# LS.net
KiCad netlist of a schematic drawn in EAGLE
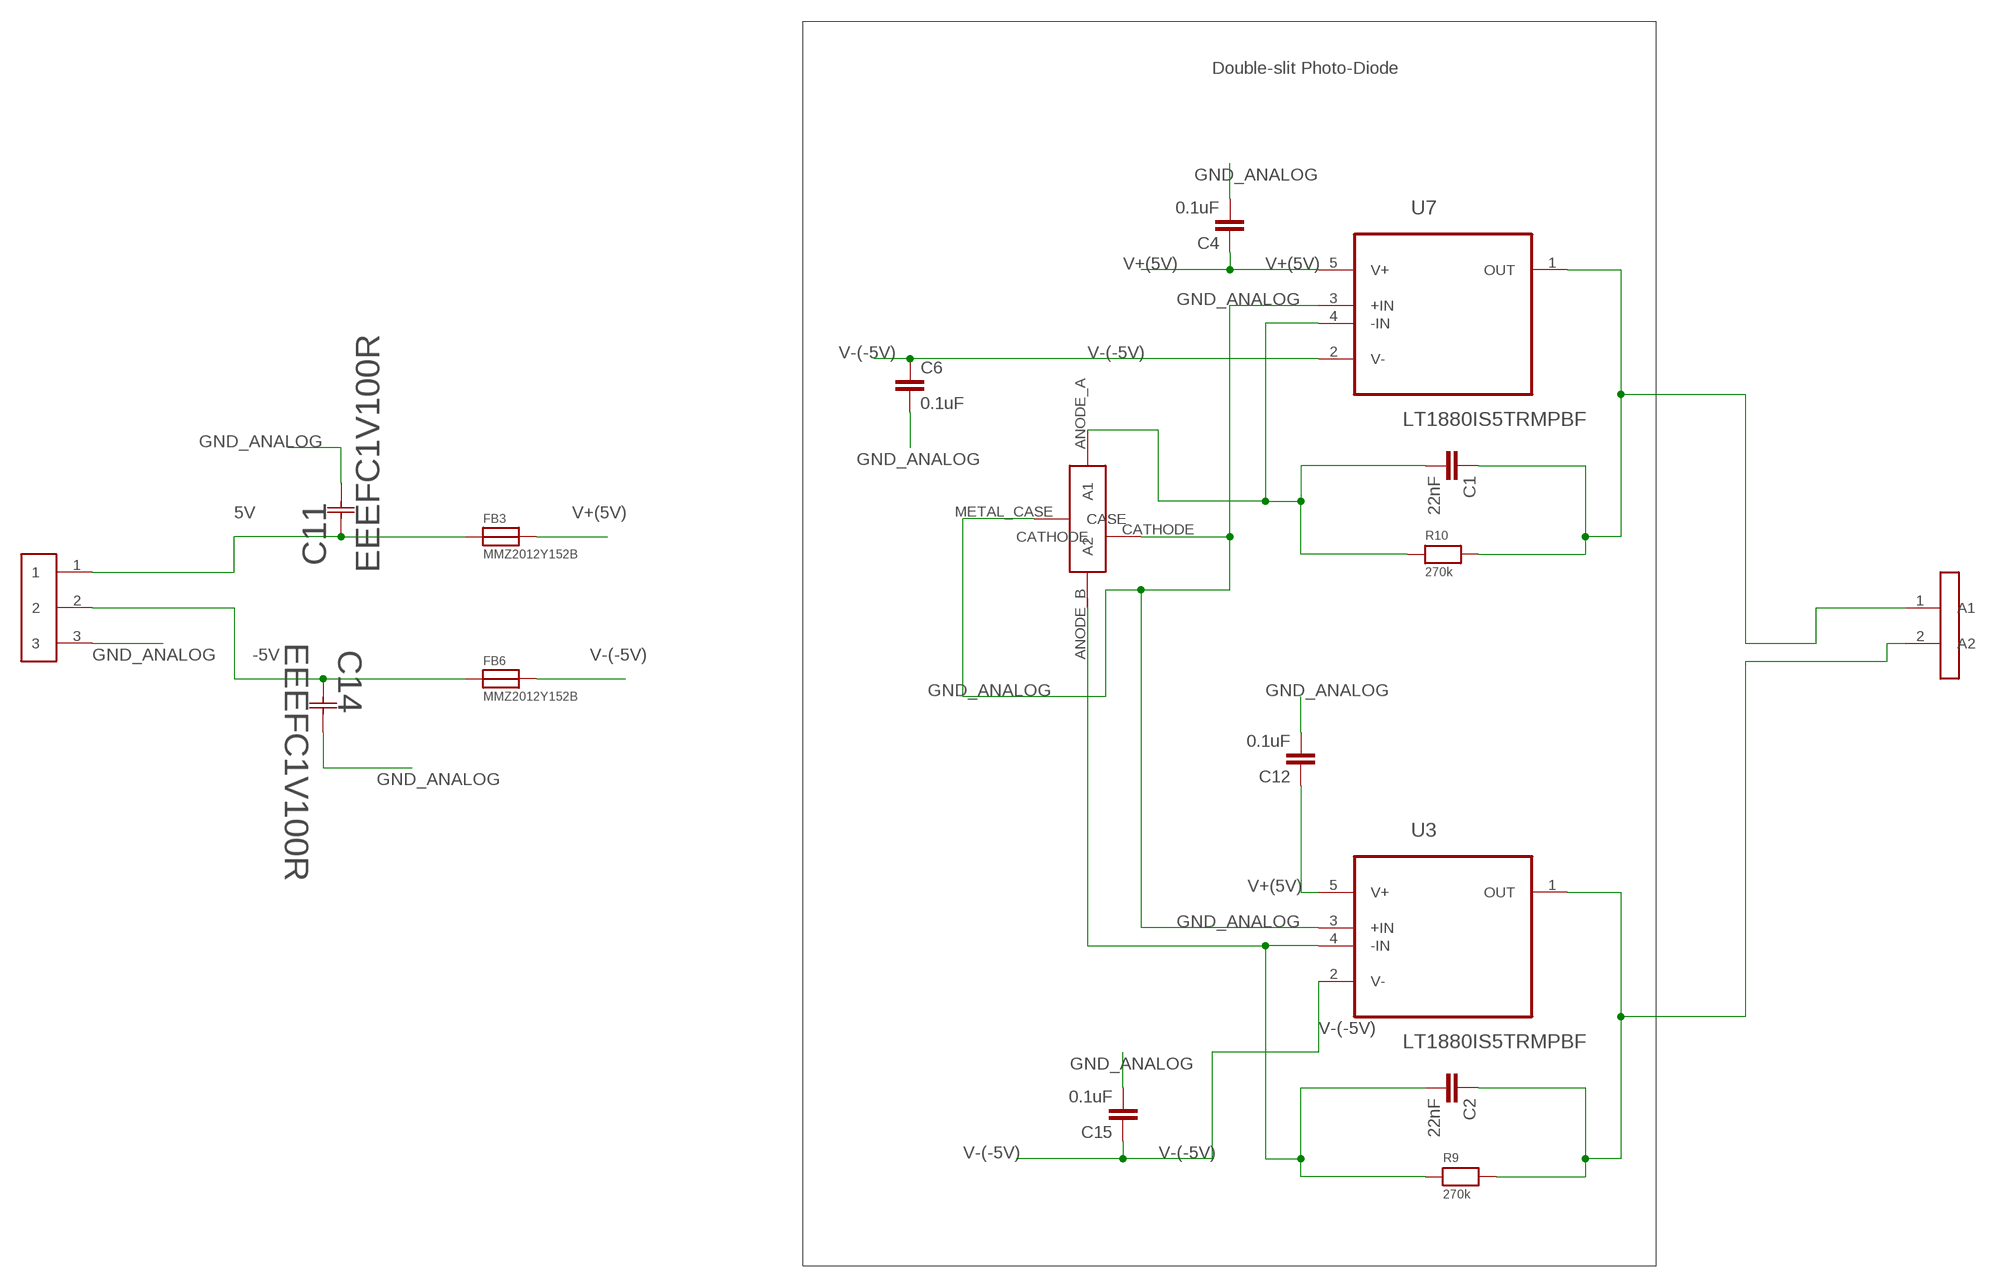
[diagram p0: schematic, sheet 1]

(export (version "E")
  (design (tool "Eeschema 10.0.6"))
  (components
    (comp (ref "C1")
      (value "22nF")
      (footprint "eagle-import:C0603")
      (libsource (lib "eagle-import") (part "C-EUC0603"))
    )
    (comp (ref "C2")
      (value "22nF")
      (footprint "eagle-import:C0603")
      (libsource (lib "eagle-import") (part "C-EUC0603"))
    )
    (comp (ref "C4")
      (value "0.1uF")
      (footprint "eagle-import:C0603")
      (libsource (lib "eagle-import") (part "C-EUC0603"))
    )
    (comp (ref "C6")
      (value "0.1uF")
      (footprint "eagle-import:C0603")
      (libsource (lib "eagle-import") (part "C-EUC0603"))
    )
    (comp (ref "C11")
      (value "EEEFC1V100R")
      (footprint "eagle-import:CAP_EEFC_C")
      (libsource (lib "eagle-import") (part "EEEFC1V100R"))
    )
    (comp (ref "C12")
      (value "0.1uF")
      (footprint "eagle-import:C0603")
      (libsource (lib "eagle-import") (part "C-EUC0603"))
    )
    (comp (ref "C14")
      (value "EEEFC1V100R")
      (footprint "eagle-import:CAP_EEFC_C")
      (libsource (lib "eagle-import") (part "EEEFC1V100R"))
    )
    (comp (ref "C15")
      (value "0.1uF")
      (footprint "eagle-import:C0603")
      (libsource (lib "eagle-import") (part "C-EUC0603"))
    )
    (comp (ref "FB3")
      (value "MMZ2012Y152B")
      (footprint "eagle-import:0805")
      (libsource (lib "eagle-import") (part "FERRITE0805"))
    )
    (comp (ref "FB6")
      (value "MMZ2012Y152B")
      (footprint "eagle-import:0805")
      (libsource (lib "eagle-import") (part "FERRITE0805"))
    )
    (comp (ref "J2")
      (value "22-28-8020")
      (footprint "eagle-import:22-28-8020")
      (fields (field (name "MANUFACTURER_PART_NUMBER") "22288020"))
      (libsource (lib "eagle-import") (part "22-28-8020"))
    )
    (comp (ref "R9")
      (value "270k")
      (footprint "eagle-import:0805")
      (libsource (lib "eagle-import") (part "RESISTOR0805"))
    )
    (comp (ref "R10")
      (value "270k")
      (footprint "eagle-import:0805")
      (libsource (lib "eagle-import") (part "RESISTOR0805"))
    )
    (comp (ref "U$1")
      (value "SFH221")
      (footprint "eagle-import:SFH_221")
      (libsource (lib "eagle-import") (part "SFH221"))
    )
    (comp (ref "U$2")
      (value "PINHD_SMD-3")
      (footprint "eagle-import:PINHD_SMD-3")
      (libsource (lib "eagle-import") (part "PINHD_SMD-3"))
    )
    (comp (ref "U3")
      (value "LT1880IS5TRMPBF")
      (footprint "eagle-import:SOT95P280X100-5N")
      (fields
        (field (name "DIGI-KEY_PART_NUMBER") "LT1880IS5#TRMPBFCT-ND")
        (field (name "MF") "Linear Technology")
        (field (name "MP") "LT1880IS5#TRMPBF")
      )
      (libsource (lib "eagle-import") (part "LT1880IS5TRMPBF"))
    )
    (comp (ref "U7")
      (value "LT1880IS5TRMPBF")
      (footprint "eagle-import:SOT95P280X100-5N")
      (fields
        (field (name "DIGI-KEY_PART_NUMBER") "LT1880IS5#TRMPBFCT-ND")
        (field (name "MF") "Linear Technology")
        (field (name "MP") "LT1880IS5#TRMPBF")
      )
      (libsource (lib "eagle-import") (part "LT1880IS5TRMPBF"))
    )
  )
  (nets
    (net (code "1") (name "/-5V") (class "Default")
      (node (ref "C14") (pin "1") (pinfunction "11_1") (pintype "passive"))
      (node (ref "FB6") (pin "1") (pinfunction "P$1_1") (pintype "bidirectional"))
      (node (ref "U$2") (pin "2") (pinfunction "2_2") (pintype "bidirectional"))
    )
    (net (code "2") (name "/5V") (class "Default")
      (node (ref "C11") (pin "1") (pinfunction "11_1") (pintype "passive"))
      (node (ref "FB3") (pin "1") (pinfunction "P$1_1") (pintype "bidirectional"))
      (node (ref "U$2") (pin "1") (pinfunction "1_1") (pintype "bidirectional"))
    )
    (net (code "3") (name "/GND_ANALOG") (class "Default")
      (node (ref "C11") (pin "2") (pinfunction "22_2") (pintype "passive"))
      (node (ref "C12") (pin "2") (pinfunction "2_2") (pintype "passive"))
      (node (ref "C14") (pin "2") (pinfunction "22_2") (pintype "passive"))
      (node (ref "C15") (pin "2") (pinfunction "2_2") (pintype "passive"))
      (node (ref "C4") (pin "2") (pinfunction "2_2") (pintype "passive"))
      (node (ref "C6") (pin "2") (pinfunction "2_2") (pintype "passive"))
      (node (ref "U$1") (pin "CATHODE") (pinfunction "CATHODE_CATHODE") (pintype "bidirectional"))
      (node (ref "U$1") (pin "METAL_CASE") (pinfunction "CASE_METAL_CASE") (pintype "bidirectional"))
      (node (ref "U$2") (pin "3") (pinfunction "3_3") (pintype "bidirectional"))
      (node (ref "U3") (pin "3") (pinfunction "+IN_3") (pintype "input"))
      (node (ref "U7") (pin "3") (pinfunction "+IN_3") (pintype "input"))
    )
    (net (code "4") (name "/V+(5V)") (class "Default")
      (node (ref "C12") (pin "1") (pinfunction "1_1") (pintype "passive"))
      (node (ref "C4") (pin "1") (pinfunction "1_1") (pintype "passive"))
      (node (ref "FB3") (pin "2") (pinfunction "P$2_2") (pintype "bidirectional"))
      (node (ref "U3") (pin "5") (pinfunction "V+_5") (pintype "power_in"))
      (node (ref "U7") (pin "5") (pinfunction "V+_5") (pintype "power_in"))
    )
    (net (code "5") (name "/V-(-5V)") (class "Default")
      (node (ref "C15") (pin "1") (pinfunction "1_1") (pintype "passive"))
      (node (ref "C6") (pin "1") (pinfunction "1_1") (pintype "passive"))
      (node (ref "FB6") (pin "2") (pinfunction "P$2_2") (pintype "bidirectional"))
      (node (ref "U3") (pin "2") (pinfunction "V-_2") (pintype "power_in"))
      (node (ref "U7") (pin "2") (pinfunction "V-_2") (pintype "power_in"))
    )
    (net (code "6") (name "Net-(J2-A1)") (class "Default")
      (node (ref "C1") (pin "1") (pinfunction "1_1") (pintype "passive"))
      (node (ref "J2") (pin "1") (pinfunction "A1_1") (pintype "passive"))
      (node (ref "R10") (pin "2") (pinfunction "2_2") (pintype "passive"))
      (node (ref "U7") (pin "1") (pinfunction "OUT_1") (pintype "output"))
    )
    (net (code "7") (name "Net-(J2-A2)") (class "Default")
      (node (ref "C2") (pin "1") (pinfunction "1_1") (pintype "passive"))
      (node (ref "J2") (pin "2") (pinfunction "A2_2") (pintype "passive"))
      (node (ref "R9") (pin "2") (pinfunction "2_2") (pintype "passive"))
      (node (ref "U3") (pin "1") (pinfunction "OUT_1") (pintype "output"))
    )
    (net (code "8") (name "Net-(U$1-A1)") (class "Default")
      (node (ref "C1") (pin "2") (pinfunction "2_2") (pintype "passive"))
      (node (ref "R10") (pin "1") (pinfunction "1_1") (pintype "passive"))
      (node (ref "U$1") (pin "ANODE_A") (pinfunction "A1_ANODE_A") (pintype "bidirectional"))
      (node (ref "U7") (pin "4") (pinfunction "-IN_4") (pintype "input"))
    )
    (net (code "9") (name "Net-(U$1-A2)") (class "Default")
      (node (ref "C2") (pin "2") (pinfunction "2_2") (pintype "passive"))
      (node (ref "R9") (pin "1") (pinfunction "1_1") (pintype "passive"))
      (node (ref "U$1") (pin "ANODE_B") (pinfunction "A2_ANODE_B") (pintype "bidirectional"))
      (node (ref "U3") (pin "4") (pinfunction "-IN_4") (pintype "input"))
    )
  )
)
